# 05_CONNECTOR_IN.net
KiCad netlist of a schematic drawn in Altium Designer
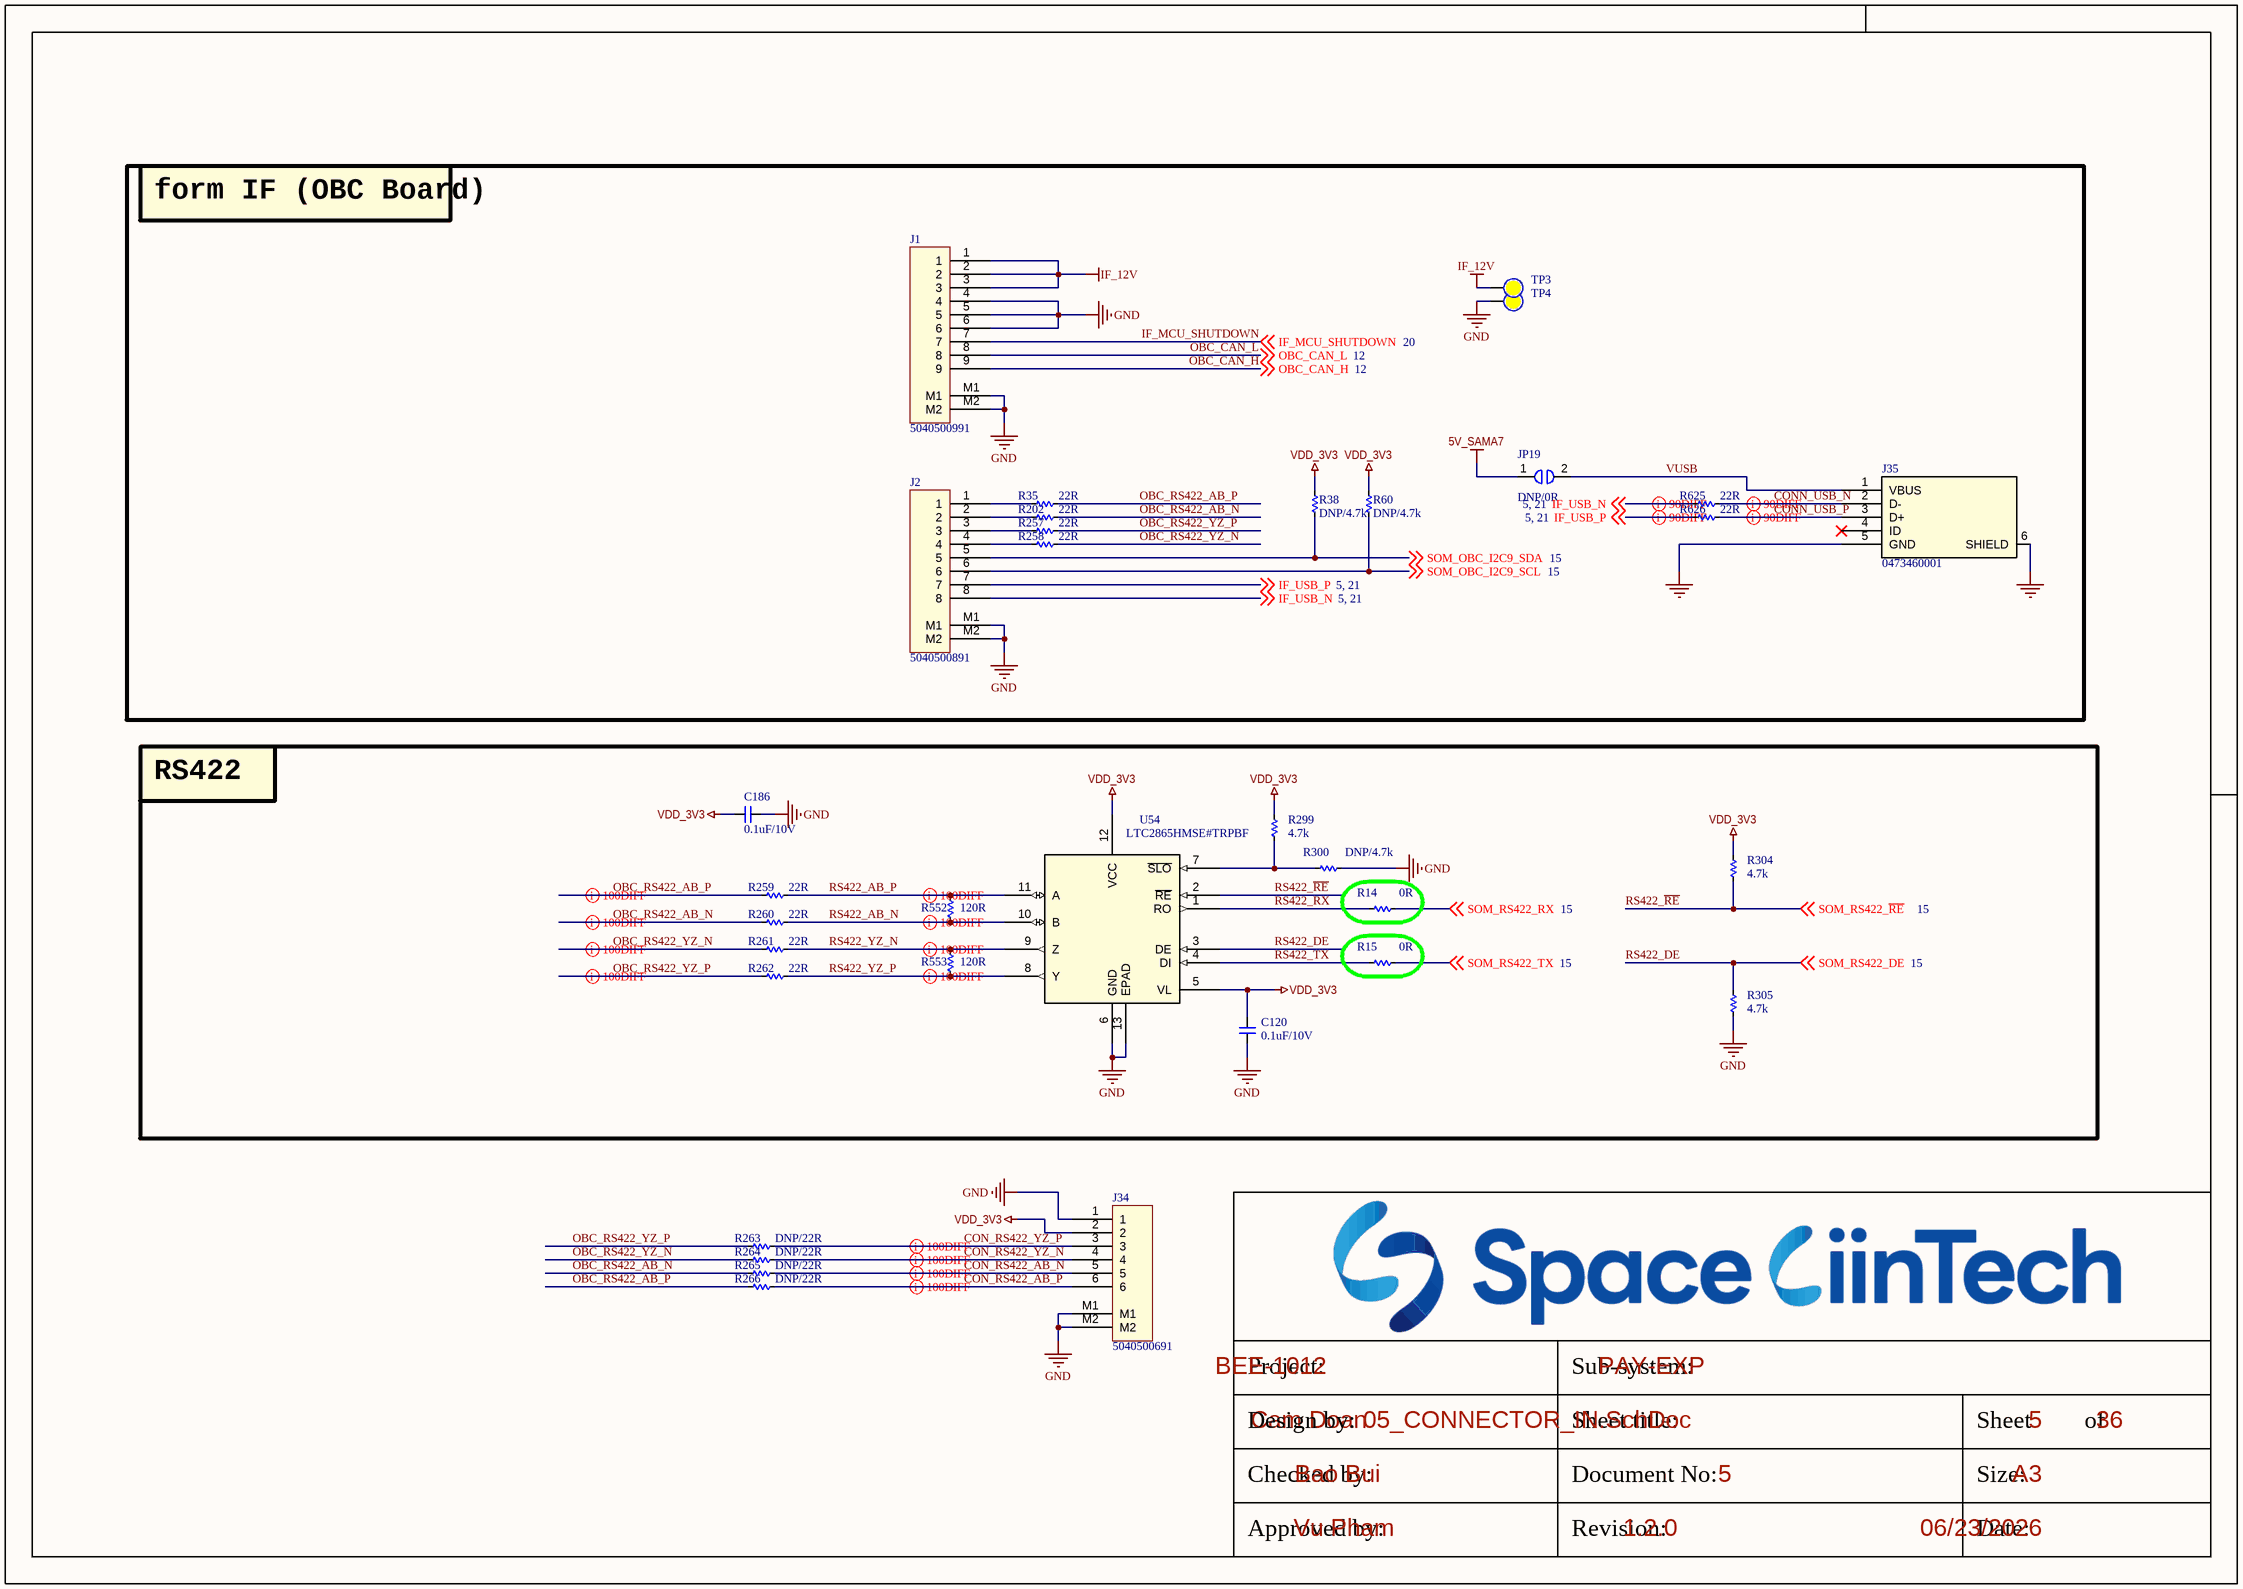
[diagram p0: 05_CONNECTOR_IN.SchDoc]

(export (version "E")
  (design (tool "Eeschema 10.0.6"))
  (components
    (comp (ref "C120")
      (value "0.1uF/10V")
      (footprint "CAP_C_1005X60")
      (description "CAP CHIP")
      (libsource (lib "LABLIB") (part "_CAP_C_2"))
    )
    (comp (ref "C186")
      (value "0.1uF/10V")
      (footprint "CAP_C_1005X60")
      (description "CAP CHIP")
      (libsource (lib "LABLIB") (part "_CAP_C_2"))
    )
    (comp (ref "J1")
      (value "5040500991")
      (footprint "MOLEX_5040500991")
      (libsource (lib "LABLIB") (part "Header 9x1_2M"))
    )
    (comp (ref "J2")
      (value "5040500891")
      (footprint "MOLEX_5040500891")
      (libsource (lib "LABLIB") (part "Header 8x1_2M"))
    )
    (comp (ref "J34")
      (value "5040500691")
      (footprint "MOLEX_5040500691")
      (libsource (lib "LABLIB") (part "Header 6x1_2M"))
    )
    (comp (ref "J35")
      (value "0473460001")
      (footprint "47346-0001_MOL")
      (description "No Description Available")
      (libsource (lib "obc_ver2") (part "USB_micro"))
    )
    (comp (ref "JP19")
      (value "DNP/0R")
      (footprint "RES_C_1608X60")
      (libsource (lib "LABLIB") (part "JUMPER_1_1"))
    )
    (comp (ref "R14")
      (value "0R")
      (footprint "RES_C_1005X40")
      (description "RES")
      (libsource (lib "LABLIB") (part "_RES_B_2"))
    )
    (comp (ref "R15")
      (value "0R")
      (footprint "RES_C_1005X40")
      (description "RES")
      (libsource (lib "LABLIB") (part "_RES_B_2"))
    )
    (comp (ref "R35")
      (value "22R")
      (footprint "RES_C_1005X40")
      (description "RES")
      (libsource (lib "LABLIB") (part "_RES_B_2"))
    )
    (comp (ref "R38")
      (value "DNP/4.7k")
      (footprint "RES_C_1005X40")
      (description "RES")
      (libsource (lib "LABLIB") (part "_RES_B_2"))
    )
    (comp (ref "R60")
      (value "DNP/4.7k")
      (footprint "RES_C_1005X40")
      (description "RES")
      (libsource (lib "LABLIB") (part "_RES_B_2"))
    )
    (comp (ref "R202")
      (value "22R")
      (footprint "RES_C_1005X40")
      (description "RES")
      (libsource (lib "LABLIB") (part "_RES_B_2"))
    )
    (comp (ref "R257")
      (value "22R")
      (footprint "RES_C_1005X40")
      (description "RES")
      (libsource (lib "LABLIB") (part "_RES_B_2"))
    )
    (comp (ref "R258")
      (value "22R")
      (footprint "RES_C_1005X40")
      (description "RES")
      (libsource (lib "LABLIB") (part "_RES_B_2"))
    )
    (comp (ref "R259")
      (value "22R")
      (footprint "RES_C_1005X40")
      (description "RES")
      (libsource (lib "LABLIB") (part "_RES_B_2"))
    )
    (comp (ref "R260")
      (value "22R")
      (footprint "RES_C_1005X40")
      (description "RES")
      (libsource (lib "LABLIB") (part "_RES_B_2"))
    )
    (comp (ref "R261")
      (value "22R")
      (footprint "RES_C_1005X40")
      (description "RES")
      (libsource (lib "LABLIB") (part "_RES_B_2"))
    )
    (comp (ref "R262")
      (value "22R")
      (footprint "RES_C_1005X40")
      (description "RES")
      (libsource (lib "LABLIB") (part "_RES_B_2"))
    )
    (comp (ref "R263")
      (value "DNP/22R")
      (footprint "RES_C_1005X40")
      (description "RES")
      (libsource (lib "LABLIB") (part "_RES_B_2"))
    )
    (comp (ref "R264")
      (value "DNP/22R")
      (footprint "RES_C_1005X40")
      (description "RES")
      (libsource (lib "LABLIB") (part "_RES_B_2"))
    )
    (comp (ref "R265")
      (value "DNP/22R")
      (footprint "RES_C_1005X40")
      (description "RES")
      (libsource (lib "LABLIB") (part "_RES_B_2"))
    )
    (comp (ref "R266")
      (value "DNP/22R")
      (footprint "RES_C_1005X40")
      (description "RES")
      (libsource (lib "LABLIB") (part "_RES_B_2"))
    )
    (comp (ref "R299")
      (value "4.7k")
      (footprint "RES_C_1005X40")
      (description "RES")
      (libsource (lib "LABLIB") (part "_RES_B_2"))
    )
    (comp (ref "R300")
      (value "DNP/4.7k")
      (footprint "RES_C_1005X40")
      (description "RES")
      (libsource (lib "LABLIB") (part "_RES_B_2"))
    )
    (comp (ref "R304")
      (value "4.7k")
      (footprint "RES_C_1005X40")
      (description "RES")
      (libsource (lib "LABLIB") (part "_RES_B_2"))
    )
    (comp (ref "R305")
      (value "4.7k")
      (footprint "RES_C_1005X40")
      (description "RES")
      (libsource (lib "LABLIB") (part "_RES_B_2"))
    )
    (comp (ref "R552")
      (value "120R")
      (footprint "RES_C_1005X40")
      (description "RES")
      (libsource (lib "LABLIB") (part "_RES_B_2"))
    )
    (comp (ref "R553")
      (value "120R")
      (footprint "RES_C_1005X40")
      (description "RES")
      (libsource (lib "LABLIB") (part "_RES_B_2"))
    )
    (comp (ref "R625")
      (value "22R")
      (footprint "RES_C_1005X40")
      (description "RES")
      (libsource (lib "LABLIB") (part "_RES_B_2"))
    )
    (comp (ref "R626")
      (value "22R")
      (footprint "RES_C_1005X40")
      (description "RES")
      (libsource (lib "LABLIB") (part "_RES_B_2"))
    )
    (comp (ref "TP3")
      (value "~")
      (footprint "Testpoint_TH_D130H80")
      (description "Test Point")
      (libsource (lib "LABLIB") (part "Test Point"))
    )
    (comp (ref "TP4")
      (value "~")
      (footprint "Testpoint_TH_D130H80")
      (description "Test Point")
      (libsource (lib "LABLIB") (part "Test Point"))
    )
    (comp (ref "U54")
      (value "LTC2865HMSE#TRPBF")
      (footprint "MSOP-12_MSE_LIT")
      (description "Â±60V Fault Protected 3V to 5.5V RS485/RS422 Transceivers")
      (fields (field (name "COPYRIGHT") "Copyright (C) 2025 Ultra Librarian. All rights reserved."))
      (libsource (lib "LABLIB") (part "LTC2865HMSETRPBF"))
    )
  )
  (nets
    (net (code "1") (name "/CONN_USB_N") (class "Default")
      (node (ref "J35") (pin "2") (pinfunction "D-_2") (pintype "passive"))
      (node (ref "R625") (pin "2") (pinfunction "2_2") (pintype "passive"))
    )
    (net (code "2") (name "/CONN_USB_P") (class "Default")
      (node (ref "J35") (pin "3") (pinfunction "D+_3") (pintype "passive"))
      (node (ref "R626") (pin "2") (pinfunction "2_2") (pintype "passive"))
    )
    (net (code "3") (name "/CON_RS422_AB_N") (class "Default")
      (node (ref "J34") (pin "5") (pinfunction "5_5") (pintype "passive"))
      (node (ref "R265") (pin "2") (pinfunction "2_2") (pintype "passive"))
    )
    (net (code "4") (name "/CON_RS422_AB_P") (class "Default")
      (node (ref "J34") (pin "6") (pinfunction "6_6") (pintype "passive"))
      (node (ref "R266") (pin "2") (pinfunction "2_2") (pintype "passive"))
    )
    (net (code "5") (name "/CON_RS422_YZ_N") (class "Default")
      (node (ref "J34") (pin "4") (pinfunction "4_4") (pintype "passive"))
      (node (ref "R264") (pin "2") (pinfunction "2_2") (pintype "passive"))
    )
    (net (code "6") (name "/CON_RS422_YZ_P") (class "Default")
      (node (ref "J34") (pin "3") (pinfunction "3_3") (pintype "passive"))
      (node (ref "R263") (pin "2") (pinfunction "2_2") (pintype "passive"))
    )
    (net (code "7") (name "/OBC_RS422_AB_N") (class "Default")
      (node (ref "R202") (pin "2") (pinfunction "2_2") (pintype "passive"))
      (node (ref "R260") (pin "1") (pinfunction "1_1") (pintype "passive"))
      (node (ref "R265") (pin "1") (pinfunction "1_1") (pintype "passive"))
    )
    (net (code "8") (name "/OBC_RS422_AB_P") (class "Default")
      (node (ref "R259") (pin "1") (pinfunction "1_1") (pintype "passive"))
      (node (ref "R266") (pin "1") (pinfunction "1_1") (pintype "passive"))
      (node (ref "R35") (pin "2") (pinfunction "2_2") (pintype "passive"))
    )
    (net (code "9") (name "/OBC_RS422_YZ_N") (class "Default")
      (node (ref "R258") (pin "2") (pinfunction "2_2") (pintype "passive"))
      (node (ref "R261") (pin "1") (pinfunction "1_1") (pintype "passive"))
      (node (ref "R264") (pin "1") (pinfunction "1_1") (pintype "passive"))
    )
    (net (code "10") (name "/OBC_RS422_YZ_P") (class "Default")
      (node (ref "R257") (pin "2") (pinfunction "2_2") (pintype "passive"))
      (node (ref "R262") (pin "1") (pinfunction "1_1") (pintype "passive"))
      (node (ref "R263") (pin "1") (pinfunction "1_1") (pintype "passive"))
    )
    (net (code "11") (name "/RS422_AB_N") (class "Default")
      (node (ref "R260") (pin "2") (pinfunction "2_2") (pintype "passive"))
      (node (ref "R552") (pin "2") (pinfunction "2_2") (pintype "passive"))
      (node (ref "U54") (pin "10") (pinfunction "B_10") (pintype "bidirectional"))
    )
    (net (code "12") (name "/RS422_AB_P") (class "Default")
      (node (ref "R259") (pin "2") (pinfunction "2_2") (pintype "passive"))
      (node (ref "R552") (pin "1") (pinfunction "1_1") (pintype "passive"))
      (node (ref "U54") (pin "11") (pinfunction "A_11") (pintype "bidirectional"))
    )
    (net (code "13") (name "/RS422_RX") (class "Default")
      (node (ref "R14") (pin "1") (pinfunction "1_1") (pintype "passive"))
      (node (ref "U54") (pin "1") (pinfunction "RO_1") (pintype "output"))
    )
    (net (code "14") (name "/RS422_TX") (class "Default")
      (node (ref "R15") (pin "1") (pinfunction "1_1") (pintype "passive"))
      (node (ref "U54") (pin "4") (pinfunction "DI_4") (pintype "input"))
    )
    (net (code "15") (name "/RS422_YZ_N") (class "Default")
      (node (ref "R261") (pin "2") (pinfunction "2_2") (pintype "passive"))
      (node (ref "R553") (pin "1") (pinfunction "1_1") (pintype "passive"))
      (node (ref "U54") (pin "9") (pinfunction "Z_9") (pintype "output"))
    )
    (net (code "16") (name "/RS422_YZ_P") (class "Default")
      (node (ref "R262") (pin "2") (pinfunction "2_2") (pintype "passive"))
      (node (ref "R553") (pin "2") (pinfunction "2_2") (pintype "passive"))
      (node (ref "U54") (pin "8") (pinfunction "Y_8") (pintype "output"))
    )
    (net (code "17") (name "/VUSB") (class "Default")
      (node (ref "J35") (pin "1") (pinfunction "VBUS_1") (pintype "passive"))
      (node (ref "JP19") (pin "2") (pinfunction "2_2") (pintype "passive"))
    )
    (net (code "18") (name "5V_SAMA7") (class "Default")
      (node (ref "JP19") (pin "1") (pinfunction "1_1") (pintype "passive"))
    )
    (net (code "19") (name "GND") (class "Default")
      (node (ref "C120") (pin "1") (pinfunction "1_1") (pintype "passive"))
      (node (ref "C186") (pin "1") (pinfunction "1_1") (pintype "passive"))
      (node (ref "J1") (pin "4") (pinfunction "4_4") (pintype "passive"))
      (node (ref "J1") (pin "5") (pinfunction "5_5") (pintype "passive"))
      (node (ref "J1") (pin "6") (pinfunction "6_6") (pintype "passive"))
      (node (ref "J1") (pin "M1") (pinfunction "M1_M1") (pintype "passive"))
      (node (ref "J1") (pin "M2") (pinfunction "M2_M2") (pintype "passive"))
      (node (ref "J2") (pin "M1") (pinfunction "M1_M1") (pintype "passive"))
      (node (ref "J2") (pin "M2") (pinfunction "M2_M2") (pintype "passive"))
      (node (ref "J34") (pin "1") (pinfunction "1_1") (pintype "passive"))
      (node (ref "J34") (pin "M1") (pinfunction "M1_M1") (pintype "passive"))
      (node (ref "J34") (pin "M2") (pinfunction "M2_M2") (pintype "passive"))
      (node (ref "J35") (pin "5") (pinfunction "GND_5") (pintype "power_in"))
      (node (ref "J35") (pin "6") (pinfunction "SHIELD_6") (pintype "passive"))
      (node (ref "R300") (pin "2") (pinfunction "2_2") (pintype "passive"))
      (node (ref "R305") (pin "1") (pinfunction "1_1") (pintype "passive"))
      (node (ref "TP4") (pin "1") (pinfunction "1_1") (pintype "passive"))
      (node (ref "U54") (pin "13") (pinfunction "EPAD_13") (pintype "passive"))
      (node (ref "U54") (pin "6") (pinfunction "GND_6") (pintype "power_in"))
    )
    (net (code "20") (name "IF_12V") (class "Default")
      (node (ref "J1") (pin "1") (pinfunction "1_1") (pintype "passive"))
      (node (ref "J1") (pin "2") (pinfunction "2_2") (pintype "passive"))
      (node (ref "J1") (pin "3") (pinfunction "3_3") (pintype "passive"))
      (node (ref "TP3") (pin "1") (pinfunction "1_1") (pintype "passive"))
    )
    (net (code "21") (name "IF_MCU_SHUTDOWN") (class "Default")
      (node (ref "J1") (pin "7") (pinfunction "7_7") (pintype "passive"))
    )
    (net (code "22") (name "IF_USB_N") (class "Default")
      (node (ref "J2") (pin "8") (pinfunction "8_8") (pintype "passive"))
      (node (ref "R625") (pin "1") (pinfunction "1_1") (pintype "passive"))
    )
    (net (code "23") (name "IF_USB_P") (class "Default")
      (node (ref "J2") (pin "7") (pinfunction "7_7") (pintype "passive"))
      (node (ref "R626") (pin "1") (pinfunction "1_1") (pintype "passive"))
    )
    (net (code "24") (name "Net-(J2-Pad1)") (class "Default")
      (node (ref "J2") (pin "1") (pinfunction "1_1") (pintype "passive"))
      (node (ref "R35") (pin "1") (pinfunction "1_1") (pintype "passive"))
    )
    (net (code "25") (name "Net-(J2-Pad2)") (class "Default")
      (node (ref "J2") (pin "2") (pinfunction "2_2") (pintype "passive"))
      (node (ref "R202") (pin "1") (pinfunction "1_1") (pintype "passive"))
    )
    (net (code "26") (name "Net-(J2-Pad3)") (class "Default")
      (node (ref "J2") (pin "3") (pinfunction "3_3") (pintype "passive"))
      (node (ref "R257") (pin "1") (pinfunction "1_1") (pintype "passive"))
    )
    (net (code "27") (name "Net-(J2-Pad4)") (class "Default")
      (node (ref "J2") (pin "4") (pinfunction "4_4") (pintype "passive"))
      (node (ref "R258") (pin "1") (pinfunction "1_1") (pintype "passive"))
    )
    (net (code "28") (name "Net-(U54-~{SLO})") (class "Default")
      (node (ref "R299") (pin "2") (pinfunction "2_2") (pintype "passive"))
      (node (ref "R300") (pin "1") (pinfunction "1_1") (pintype "passive"))
      (node (ref "U54") (pin "7") (pinfunction "~{SLO}_7") (pintype "input"))
    )
    (net (code "29") (name "OBC_CAN_H") (class "Default")
      (node (ref "J1") (pin "9") (pinfunction "9_9") (pintype "passive"))
    )
    (net (code "30") (name "OBC_CAN_L") (class "Default")
      (node (ref "J1") (pin "8") (pinfunction "8_8") (pintype "passive"))
    )
    (net (code "31") (name "SOM_OBC_I2C9_SCL") (class "Default")
      (node (ref "J2") (pin "6") (pinfunction "6_6") (pintype "passive"))
      (node (ref "R60") (pin "2") (pinfunction "2_2") (pintype "passive"))
    )
    (net (code "32") (name "SOM_OBC_I2C9_SDA") (class "Default")
      (node (ref "J2") (pin "5") (pinfunction "5_5") (pintype "passive"))
      (node (ref "R38") (pin "2") (pinfunction "2_2") (pintype "passive"))
    )
    (net (code "33") (name "SOM_RS422_DE") (class "Default")
      (node (ref "R305") (pin "2") (pinfunction "2_2") (pintype "passive"))
      (node (ref "U54") (pin "3") (pinfunction "DE_3") (pintype "input"))
    )
    (net (code "34") (name "SOM_RS422_RX") (class "Default")
      (node (ref "R14") (pin "2") (pinfunction "2_2") (pintype "passive"))
    )
    (net (code "35") (name "SOM_RS422_TX") (class "Default")
      (node (ref "R15") (pin "2") (pinfunction "2_2") (pintype "passive"))
    )
    (net (code "36") (name "SOM_RS422_~{RE}") (class "Default")
      (node (ref "R304") (pin "2") (pinfunction "2_2") (pintype "passive"))
      (node (ref "U54") (pin "2") (pinfunction "~{RE}_2") (pintype "input"))
    )
    (net (code "37") (name "VDD_3V3") (class "Default")
      (node (ref "C120") (pin "2") (pinfunction "2_2") (pintype "passive"))
      (node (ref "C186") (pin "2") (pinfunction "2_2") (pintype "passive"))
      (node (ref "J34") (pin "2") (pinfunction "2_2") (pintype "passive"))
      (node (ref "R299") (pin "1") (pinfunction "1_1") (pintype "passive"))
      (node (ref "R304") (pin "1") (pinfunction "1_1") (pintype "passive"))
      (node (ref "R38") (pin "1") (pinfunction "1_1") (pintype "passive"))
      (node (ref "R60") (pin "1") (pinfunction "1_1") (pintype "passive"))
      (node (ref "U54") (pin "12") (pinfunction "VCC_12") (pintype "power_in"))
      (node (ref "U54") (pin "5") (pinfunction "VL_5") (pintype "power_in"))
    )
    (net (code "38") (name "unconnected-(J35-ID-Pad4)") (class "Default")
      (node (ref "J35") (pin "4") (pinfunction "ID_4") (pintype "passive+no_connect"))
    )
  )
)
